# ENGI301_clearasteroids.net
KiCad netlist of a schematic drawn in EAGLE
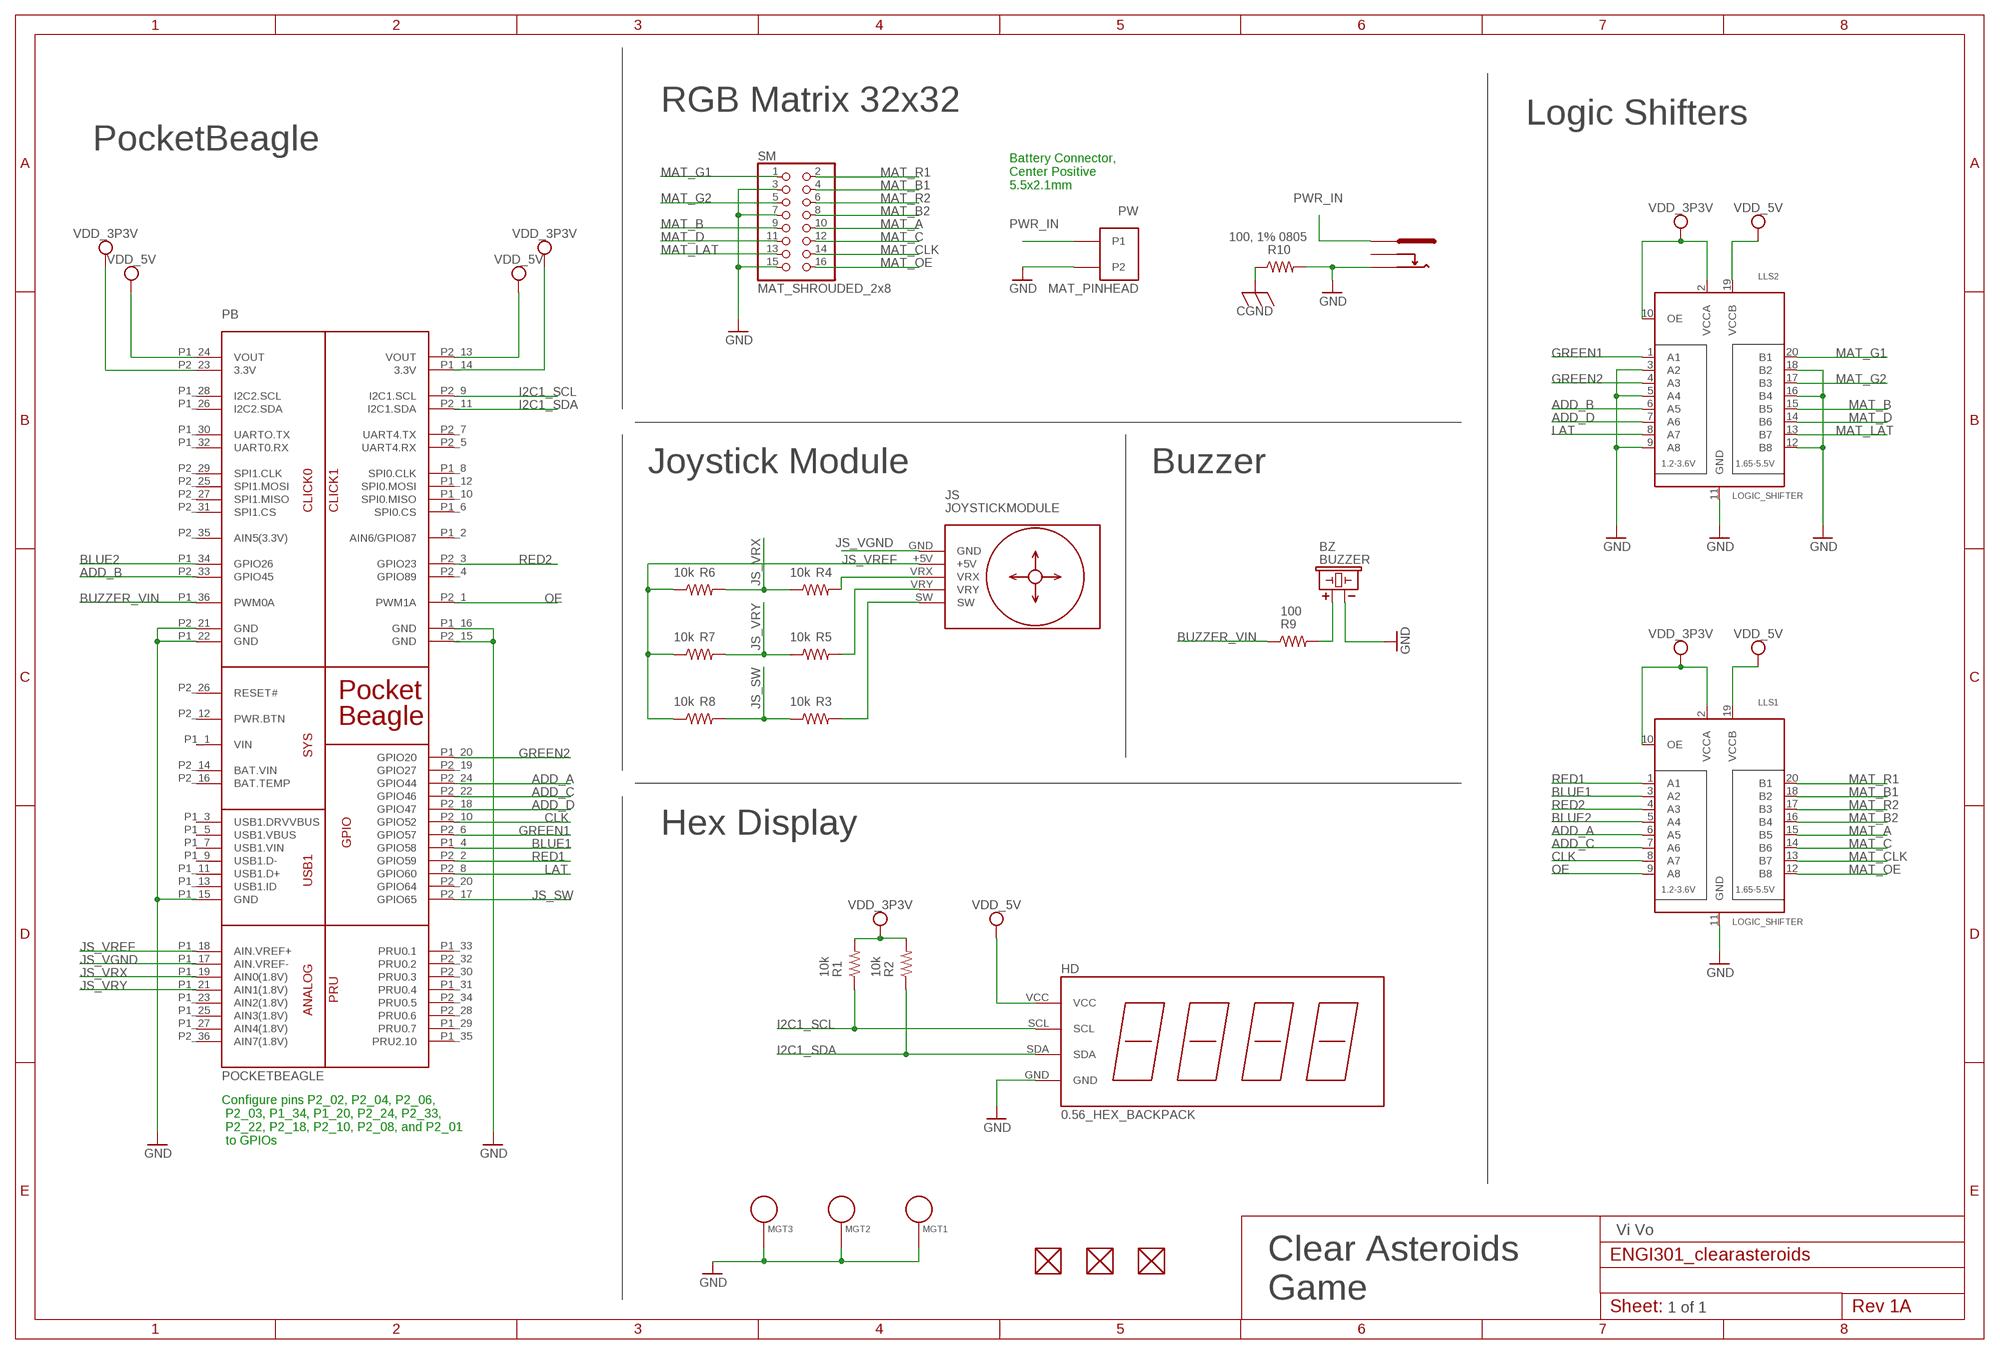
[diagram p0: schematic, sheet 1]

(export (version "E")
  (design (tool "Eeschema 10.0.6"))
  (components
    (comp (ref "BC")
      (value "GHI_PJ-102B_POWER_CON")
      (footprint "eagle-import:GHI_PJ-102B_POWER_CON")
      (libsource (lib "eagle-import") (part "GHI_PJ-102B_POWER_CON"))
    )
    (comp (ref "BZ")
      (value "BUZZER")
      (footprint "eagle-import:BUZZER_6.5MM")
      (libsource (lib "eagle-import") (part "BUZZER"))
    )
    (comp (ref "FUD1")
      (value "FIDUCIAL")
      (footprint "eagle-import:FIDUCIAL_40MIL")
      (libsource (lib "eagle-import") (part "FIDUCIAL"))
    )
    (comp (ref "FUD2")
      (value "FIDUCIAL")
      (footprint "eagle-import:FIDUCIAL_40MIL")
      (libsource (lib "eagle-import") (part "FIDUCIAL"))
    )
    (comp (ref "FUD3")
      (value "FIDUCIAL")
      (footprint "eagle-import:FIDUCIAL_40MIL")
      (libsource (lib "eagle-import") (part "FIDUCIAL"))
    )
    (comp (ref "HD")
      (value "0.56_HEX_BACKPACK")
      (footprint "eagle-import:0.56_HEX_BACKPACK")
      (libsource (lib "eagle-import") (part "0.56_HEX_BACKPACK"))
    )
    (comp (ref "JS")
      (value "JOYSTICKMODULE")
      (footprint "eagle-import:JOYSTICK-MODULE")
      (libsource (lib "eagle-import") (part "JOYSTICKMODULE"))
    )
    (comp (ref "LLS1")
      (value "LOGIC_SHIFTER")
      (footprint "eagle-import:TSSOP20")
      (libsource (lib "eagle-import") (part "TXB0108PWR"))
    )
    (comp (ref "LLS2")
      (value "LOGIC_SHIFTER")
      (footprint "eagle-import:TSSOP20")
      (libsource (lib "eagle-import") (part "TXB0108PWR"))
    )
    (comp (ref "MGT1")
      (value "MOUNTING_HOLE")
      (footprint "eagle-import:MOUNTING_HOLE")
      (libsource (lib "eagle-import") (part "MOUNTING_HOLE"))
    )
    (comp (ref "MGT2")
      (value "MOUNTING_HOLE")
      (footprint "eagle-import:MOUNTING_HOLE")
      (libsource (lib "eagle-import") (part "MOUNTING_HOLE"))
    )
    (comp (ref "MGT3")
      (value "MOUNTING_HOLE")
      (footprint "eagle-import:MOUNTING_HOLE")
      (libsource (lib "eagle-import") (part "MOUNTING_HOLE"))
    )
    (comp (ref "PB")
      (value "POCKETBEAGLE")
      (footprint "eagle-import:POCKETBEAGLE")
      (libsource (lib "eagle-import") (part "POCKETBEAGLE"))
    )
    (comp (ref "PW")
      (value "MAT_PINHEAD")
      (footprint "eagle-import:MSHIELD_TERMBLOCK508")
      (libsource (lib "eagle-import") (part "MAT_PINHEAD"))
    )
    (comp (ref "R1")
      (value "10k")
      (footprint "eagle-import:R1206")
      (libsource (lib "eagle-import") (part "R_R1206"))
    )
    (comp (ref "R2")
      (value "10k")
      (footprint "eagle-import:R1206")
      (libsource (lib "eagle-import") (part "R_R1206"))
    )
    (comp (ref "R3")
      (value "10k")
      (footprint "eagle-import:R1206")
      (libsource (lib "eagle-import") (part "R_R1206"))
    )
    (comp (ref "R4")
      (value "10k")
      (footprint "eagle-import:R1206")
      (libsource (lib "eagle-import") (part "R_R1206"))
    )
    (comp (ref "R5")
      (value "10k")
      (footprint "eagle-import:R1206")
      (libsource (lib "eagle-import") (part "R_R1206"))
    )
    (comp (ref "R6")
      (value "10k")
      (footprint "eagle-import:R1206")
      (libsource (lib "eagle-import") (part "R_R1206"))
    )
    (comp (ref "R7")
      (value "10k")
      (footprint "eagle-import:R1206")
      (libsource (lib "eagle-import") (part "R_R1206"))
    )
    (comp (ref "R8")
      (value "10k")
      (footprint "eagle-import:R1206")
      (libsource (lib "eagle-import") (part "R_R1206"))
    )
    (comp (ref "R9")
      (value "100")
      (footprint "eagle-import:R1206")
      (libsource (lib "eagle-import") (part "R_R1206"))
    )
    (comp (ref "R10")
      (value "100, 1% 0805")
      (footprint "eagle-import:R1206")
      (libsource (lib "eagle-import") (part "R_R1206"))
    )
    (comp (ref "SM")
      (value "MAT_SHROUDED_2x8")
      (footprint "eagle-import:MICROBUILDER_2X08_SHROUDEDSMT")
      (libsource (lib "eagle-import") (part "MICROBUILDER_HEADER-2X8_SHROUDEDSMT"))
    )
  )
  (nets
    (net (code "1") (name "/ADD_A") (class "Default")
      (node (ref "LLS1") (pin "6") (pinfunction "A5_6") (pintype "bidirectional"))
      (node (ref "PB") (pin "P2_24") (pinfunction "GPIO44_P2_24") (pintype "bidirectional"))
    )
    (net (code "2") (name "/ADD_B") (class "Default")
      (node (ref "LLS2") (pin "6") (pinfunction "A5_6") (pintype "bidirectional"))
      (node (ref "PB") (pin "P2_33") (pinfunction "GPIO45_P2_33") (pintype "bidirectional"))
    )
    (net (code "3") (name "/ADD_C") (class "Default")
      (node (ref "LLS1") (pin "7") (pinfunction "A6_7") (pintype "bidirectional"))
      (node (ref "PB") (pin "P2_22") (pinfunction "GPIO46_P2_22") (pintype "bidirectional"))
    )
    (net (code "4") (name "/ADD_D") (class "Default")
      (node (ref "LLS2") (pin "7") (pinfunction "A6_7") (pintype "bidirectional"))
      (node (ref "PB") (pin "P2_18") (pinfunction "GPIO47_P2_18") (pintype "bidirectional"))
    )
    (net (code "5") (name "/BLUE1") (class "Default")
      (node (ref "LLS1") (pin "3") (pinfunction "A2_3") (pintype "bidirectional"))
      (node (ref "PB") (pin "P1_4") (pinfunction "GPIO58_P1_4") (pintype "bidirectional"))
    )
    (net (code "6") (name "/BLUE2") (class "Default")
      (node (ref "LLS1") (pin "5") (pinfunction "A4_5") (pintype "bidirectional"))
      (node (ref "PB") (pin "P1_34") (pinfunction "GPIO26_P1_34") (pintype "bidirectional"))
    )
    (net (code "7") (name "/BUZZER_VIN") (class "Default")
      (node (ref "PB") (pin "P1_36") (pinfunction "PWM0A_P1_36") (pintype "bidirectional"))
      (node (ref "R9") (pin "1") (pinfunction "1_1") (pintype "passive"))
    )
    (net (code "8") (name "/CLK") (class "Default")
      (node (ref "LLS1") (pin "8") (pinfunction "A7_8") (pintype "bidirectional"))
      (node (ref "PB") (pin "P2_10") (pinfunction "GPIO52_P2_10") (pintype "bidirectional"))
    )
    (net (code "9") (name "/GREEN1") (class "Default")
      (node (ref "LLS2") (pin "1") (pinfunction "A1_1") (pintype "bidirectional"))
      (node (ref "PB") (pin "P2_6") (pinfunction "GPIO57_P2_6") (pintype "bidirectional"))
    )
    (net (code "10") (name "/GREEN2") (class "Default")
      (node (ref "LLS2") (pin "4") (pinfunction "A3_4") (pintype "bidirectional"))
      (node (ref "PB") (pin "P1_20") (pinfunction "GPIO20_P1_20") (pintype "bidirectional"))
    )
    (net (code "11") (name "/I2C1_SCL") (class "Default")
      (node (ref "HD") (pin "SCL") (pinfunction "SCL_SCL") (pintype "bidirectional"))
      (node (ref "PB") (pin "P2_9") (pinfunction "I2C1.SCL_P2_9") (pintype "bidirectional"))
      (node (ref "R1") (pin "1") (pinfunction "1_1") (pintype "passive"))
    )
    (net (code "12") (name "/I2C1_SDA") (class "Default")
      (node (ref "HD") (pin "SDA") (pinfunction "SDA_SDA") (pintype "bidirectional"))
      (node (ref "PB") (pin "P2_11") (pinfunction "I2C1.SDA_P2_11") (pintype "bidirectional"))
      (node (ref "R2") (pin "1") (pinfunction "1_1") (pintype "passive"))
    )
    (net (code "13") (name "/JS_SW") (class "Default")
      (node (ref "PB") (pin "P2_17") (pinfunction "GPIO65_P2_17") (pintype "bidirectional"))
      (node (ref "R3") (pin "1") (pinfunction "1_1") (pintype "passive"))
      (node (ref "R8") (pin "2") (pinfunction "2_2") (pintype "passive"))
    )
    (net (code "14") (name "/JS_VGND") (class "Default")
      (node (ref "JS") (pin "GND") (pinfunction "GND_GND") (pintype "power_in"))
      (node (ref "PB") (pin "P1_17") (pinfunction "AIN.VREF-_P1_17") (pintype "bidirectional"))
    )
    (net (code "15") (name "/JS_VREF") (class "Default")
      (node (ref "JS") (pin "+5V") (pinfunction "+5V_+5V") (pintype "power_in"))
      (node (ref "PB") (pin "P1_18") (pinfunction "AIN.VREF+_P1_18") (pintype "bidirectional"))
      (node (ref "R6") (pin "1") (pinfunction "1_1") (pintype "passive"))
      (node (ref "R7") (pin "1") (pinfunction "1_1") (pintype "passive"))
      (node (ref "R8") (pin "1") (pinfunction "1_1") (pintype "passive"))
    )
    (net (code "16") (name "/JS_VRX") (class "Default")
      (node (ref "PB") (pin "P1_19") (pinfunction "AIN0(1.8V)_P1_19") (pintype "bidirectional"))
      (node (ref "R4") (pin "1") (pinfunction "1_1") (pintype "passive"))
      (node (ref "R6") (pin "2") (pinfunction "2_2") (pintype "passive"))
    )
    (net (code "17") (name "/JS_VRY") (class "Default")
      (node (ref "PB") (pin "P1_21") (pinfunction "AIN1(1.8V)_P1_21") (pintype "bidirectional"))
      (node (ref "R5") (pin "1") (pinfunction "1_1") (pintype "passive"))
      (node (ref "R7") (pin "2") (pinfunction "2_2") (pintype "passive"))
    )
    (net (code "18") (name "/LAT") (class "Default")
      (node (ref "LLS2") (pin "8") (pinfunction "A7_8") (pintype "bidirectional"))
      (node (ref "PB") (pin "P2_8") (pinfunction "GPIO60_P2_8") (pintype "bidirectional"))
    )
    (net (code "19") (name "/MAT_A") (class "Default")
      (node (ref "LLS1") (pin "15") (pinfunction "B5_15") (pintype "bidirectional"))
      (node (ref "SM") (pin "10") (pinfunction "10_10") (pintype "passive"))
    )
    (net (code "20") (name "/MAT_B") (class "Default")
      (node (ref "LLS2") (pin "15") (pinfunction "B5_15") (pintype "bidirectional"))
      (node (ref "SM") (pin "9") (pinfunction "9_9") (pintype "passive"))
    )
    (net (code "21") (name "/MAT_B1") (class "Default")
      (node (ref "LLS1") (pin "18") (pinfunction "B2_18") (pintype "bidirectional"))
      (node (ref "SM") (pin "4") (pinfunction "4_4") (pintype "passive"))
    )
    (net (code "22") (name "/MAT_B2") (class "Default")
      (node (ref "LLS1") (pin "16") (pinfunction "B4_16") (pintype "bidirectional"))
      (node (ref "SM") (pin "8") (pinfunction "8_8") (pintype "passive"))
    )
    (net (code "23") (name "/MAT_C") (class "Default")
      (node (ref "LLS1") (pin "14") (pinfunction "B6_14") (pintype "bidirectional"))
      (node (ref "SM") (pin "12") (pinfunction "12_12") (pintype "passive"))
    )
    (net (code "24") (name "/MAT_CLK") (class "Default")
      (node (ref "LLS1") (pin "13") (pinfunction "B7_13") (pintype "bidirectional"))
      (node (ref "SM") (pin "14") (pinfunction "14_14") (pintype "passive"))
    )
    (net (code "25") (name "/MAT_D") (class "Default")
      (node (ref "LLS2") (pin "14") (pinfunction "B6_14") (pintype "bidirectional"))
      (node (ref "SM") (pin "11") (pinfunction "11_11") (pintype "passive"))
    )
    (net (code "26") (name "/MAT_G1") (class "Default")
      (node (ref "LLS2") (pin "20") (pinfunction "B1_20") (pintype "bidirectional"))
      (node (ref "SM") (pin "1") (pinfunction "1_1") (pintype "passive"))
    )
    (net (code "27") (name "/MAT_G2") (class "Default")
      (node (ref "LLS2") (pin "17") (pinfunction "B3_17") (pintype "bidirectional"))
      (node (ref "SM") (pin "5") (pinfunction "5_5") (pintype "passive"))
    )
    (net (code "28") (name "/MAT_LAT") (class "Default")
      (node (ref "LLS2") (pin "13") (pinfunction "B7_13") (pintype "bidirectional"))
      (node (ref "SM") (pin "13") (pinfunction "13_13") (pintype "passive"))
    )
    (net (code "29") (name "/MAT_OE") (class "Default")
      (node (ref "LLS1") (pin "12") (pinfunction "B8_12") (pintype "bidirectional"))
      (node (ref "SM") (pin "16") (pinfunction "16_16") (pintype "passive"))
    )
    (net (code "30") (name "/MAT_R1") (class "Default")
      (node (ref "LLS1") (pin "20") (pinfunction "B1_20") (pintype "bidirectional"))
      (node (ref "SM") (pin "2") (pinfunction "2_2") (pintype "passive"))
    )
    (net (code "31") (name "/MAT_R2") (class "Default")
      (node (ref "LLS1") (pin "17") (pinfunction "B3_17") (pintype "bidirectional"))
      (node (ref "SM") (pin "6") (pinfunction "6_6") (pintype "passive"))
    )
    (net (code "32") (name "/OE") (class "Default")
      (node (ref "LLS1") (pin "9") (pinfunction "A8_9") (pintype "bidirectional"))
      (node (ref "PB") (pin "P2_1") (pinfunction "PWM1A_P2_1") (pintype "bidirectional"))
    )
    (net (code "33") (name "/PWR_IN") (class "Default")
      (node (ref "BC") (pin "IN") (pinfunction "IN_IN") (pintype "bidirectional"))
      (node (ref "PW") (pin "P$3") (pinfunction "P1_P$3") (pintype "bidirectional"))
    )
    (net (code "34") (name "/RED1") (class "Default")
      (node (ref "LLS1") (pin "1") (pinfunction "A1_1") (pintype "bidirectional"))
      (node (ref "PB") (pin "P2_2") (pinfunction "GPIO59_P2_2") (pintype "bidirectional"))
    )
    (net (code "35") (name "/RED2") (class "Default")
      (node (ref "LLS1") (pin "4") (pinfunction "A3_4") (pintype "bidirectional"))
      (node (ref "PB") (pin "P2_3") (pinfunction "GPIO23_P2_3") (pintype "bidirectional"))
    )
    (net (code "36") (name "CGND") (class "Default")
      (node (ref "R10") (pin "1") (pinfunction "1_1") (pintype "passive"))
    )
    (net (code "37") (name "GND") (class "Default")
      (node (ref "BC") (pin "OUT") (pinfunction "OUT_OUT") (pintype "bidirectional"))
      (node (ref "BZ") (pin "-") (pinfunction "-_-") (pintype "passive"))
      (node (ref "HD") (pin "GND") (pinfunction "GND_GND") (pintype "bidirectional"))
      (node (ref "LLS1") (pin "11") (pinfunction "GND_11") (pintype "bidirectional"))
      (node (ref "LLS2") (pin "11") (pinfunction "GND_11") (pintype "bidirectional"))
      (node (ref "LLS2") (pin "12") (pinfunction "B8_12") (pintype "bidirectional"))
      (node (ref "LLS2") (pin "16") (pinfunction "B4_16") (pintype "bidirectional"))
      (node (ref "LLS2") (pin "18") (pinfunction "B2_18") (pintype "bidirectional"))
      (node (ref "LLS2") (pin "3") (pinfunction "A2_3") (pintype "bidirectional"))
      (node (ref "LLS2") (pin "5") (pinfunction "A4_5") (pintype "bidirectional"))
      (node (ref "LLS2") (pin "9") (pinfunction "A8_9") (pintype "bidirectional"))
      (node (ref "MGT1") (pin "P$1") (pinfunction "P$1_P$1") (pintype "bidirectional"))
      (node (ref "MGT2") (pin "P$1") (pinfunction "P$1_P$1") (pintype "bidirectional"))
      (node (ref "MGT3") (pin "P$1") (pinfunction "P$1_P$1") (pintype "bidirectional"))
      (node (ref "PB") (pin "P1_15") (pinfunction "GND_P1_15") (pintype "bidirectional"))
      (node (ref "PB") (pin "P1_16") (pinfunction "GND_P1_16") (pintype "bidirectional"))
      (node (ref "PB") (pin "P1_22") (pinfunction "GND_P1_22") (pintype "bidirectional"))
      (node (ref "PB") (pin "P2_15") (pinfunction "GND_P2_15") (pintype "bidirectional"))
      (node (ref "PB") (pin "P2_21") (pinfunction "GND_P2_21") (pintype "bidirectional"))
      (node (ref "PW") (pin "P$4") (pinfunction "P2_P$4") (pintype "bidirectional"))
      (node (ref "R10") (pin "2") (pinfunction "2_2") (pintype "passive"))
      (node (ref "SM") (pin "15") (pinfunction "15_15") (pintype "passive"))
      (node (ref "SM") (pin "3") (pinfunction "3_3") (pintype "passive"))
      (node (ref "SM") (pin "7") (pinfunction "7_7") (pintype "passive"))
    )
    (net (code "38") (name "Net-(BZ-Pad+)") (class "Default")
      (node (ref "BZ") (pin "+") (pinfunction "+_+") (pintype "passive"))
      (node (ref "R9") (pin "2") (pinfunction "2_2") (pintype "passive"))
    )
    (net (code "39") (name "Net-(JS-PadSW)") (class "Default")
      (node (ref "JS") (pin "SW") (pinfunction "SW_SW") (pintype "passive"))
      (node (ref "R3") (pin "2") (pinfunction "2_2") (pintype "passive"))
    )
    (net (code "40") (name "Net-(JS-PadVRX)") (class "Default")
      (node (ref "JS") (pin "VRX") (pinfunction "VRX_VRX") (pintype "passive"))
      (node (ref "R4") (pin "2") (pinfunction "2_2") (pintype "passive"))
    )
    (net (code "41") (name "Net-(JS-PadVRY)") (class "Default")
      (node (ref "JS") (pin "VRY") (pinfunction "VRY_VRY") (pintype "passive"))
      (node (ref "R5") (pin "2") (pinfunction "2_2") (pintype "passive"))
    )
    (net (code "42") (name "VDD_3P3V") (class "Default")
      (node (ref "LLS1") (pin "10") (pinfunction "OE_10") (pintype "bidirectional"))
      (node (ref "LLS1") (pin "2") (pinfunction "VCCA_2") (pintype "bidirectional"))
      (node (ref "LLS2") (pin "10") (pinfunction "OE_10") (pintype "bidirectional"))
      (node (ref "LLS2") (pin "2") (pinfunction "VCCA_2") (pintype "bidirectional"))
      (node (ref "PB") (pin "P1_14") (pinfunction "3.3V_P1_14") (pintype "bidirectional"))
      (node (ref "PB") (pin "P2_23") (pinfunction "3.3V_P2_23") (pintype "bidirectional"))
      (node (ref "R1") (pin "2") (pinfunction "2_2") (pintype "passive"))
      (node (ref "R2") (pin "2") (pinfunction "2_2") (pintype "passive"))
    )
    (net (code "43") (name "VDD_5V") (class "Default")
      (node (ref "HD") (pin "VCC") (pinfunction "VCC_VCC") (pintype "power_in"))
      (node (ref "LLS1") (pin "19") (pinfunction "VCCB_19") (pintype "bidirectional"))
      (node (ref "LLS2") (pin "19") (pinfunction "VCCB_19") (pintype "bidirectional"))
      (node (ref "PB") (pin "P1_24") (pinfunction "VOUT_P1_24") (pintype "bidirectional"))
      (node (ref "PB") (pin "P2_13") (pinfunction "VOUT_P2_13") (pintype "bidirectional"))
    )
    (net (code "44") (name "unconnected-(BC-PadOUT_CON)") (class "Default")
      (node (ref "BC") (pin "OUT_CON") (pinfunction "OUT_CON_OUT_CON") (pintype "bidirectional"))
    )
    (net (code "45") (name "unconnected-(FUD1-PadP$1)") (class "Default")
      (node (ref "FUD1") (pin "P$1") (pinfunction "P$1_P$1") (pintype "no_connect"))
    )
    (net (code "46") (name "unconnected-(FUD2-PadP$1)") (class "Default")
      (node (ref "FUD2") (pin "P$1") (pinfunction "P$1_P$1") (pintype "no_connect"))
    )
    (net (code "47") (name "unconnected-(FUD3-PadP$1)") (class "Default")
      (node (ref "FUD3") (pin "P$1") (pinfunction "P$1_P$1") (pintype "no_connect"))
    )
    (net (code "48") (name "unconnected-(PB-AIN2(1.8V)-PadP1_23)") (class "Default")
      (node (ref "PB") (pin "P1_23") (pinfunction "AIN2(1.8V)_P1_23") (pintype "bidirectional"))
    )
    (net (code "49") (name "unconnected-(PB-AIN3(1.8V)-PadP1_25)") (class "Default")
      (node (ref "PB") (pin "P1_25") (pinfunction "AIN3(1.8V)_P1_25") (pintype "bidirectional"))
    )
    (net (code "50") (name "unconnected-(PB-AIN4(1.8V)-PadP1_27)") (class "Default")
      (node (ref "PB") (pin "P1_27") (pinfunction "AIN4(1.8V)_P1_27") (pintype "bidirectional"))
    )
    (net (code "51") (name "unconnected-(PB-AIN5(3.3V)-PadP2_35)") (class "Default")
      (node (ref "PB") (pin "P2_35") (pinfunction "AIN5(3.3V)_P2_35") (pintype "bidirectional"))
    )
    (net (code "52") (name "unconnected-(PB-AIN6{slash}GPIO87-PadP1_2)") (class "Default")
      (node (ref "PB") (pin "P1_2") (pinfunction "AIN6/GPIO87_P1_2") (pintype "bidirectional"))
    )
    (net (code "53") (name "unconnected-(PB-AIN7(1.8V)-PadP2_36)") (class "Default")
      (node (ref "PB") (pin "P2_36") (pinfunction "AIN7(1.8V)_P2_36") (pintype "bidirectional"))
    )
    (net (code "54") (name "unconnected-(PB-BAT.TEMP-PadP2_16)") (class "Default")
      (node (ref "PB") (pin "P2_16") (pinfunction "BAT.TEMP_P2_16") (pintype "bidirectional"))
    )
    (net (code "55") (name "unconnected-(PB-BAT.VIN-PadP2_14)") (class "Default")
      (node (ref "PB") (pin "P2_14") (pinfunction "BAT.VIN_P2_14") (pintype "bidirectional"))
    )
    (net (code "56") (name "unconnected-(PB-GPIO27-PadP2_19)") (class "Default")
      (node (ref "PB") (pin "P2_19") (pinfunction "GPIO27_P2_19") (pintype "bidirectional"))
    )
    (net (code "57") (name "unconnected-(PB-GPIO64-PadP2_20)") (class "Default")
      (node (ref "PB") (pin "P2_20") (pinfunction "GPIO64_P2_20") (pintype "bidirectional"))
    )
    (net (code "58") (name "unconnected-(PB-GPIO89-PadP2_4)") (class "Default")
      (node (ref "PB") (pin "P2_4") (pinfunction "GPIO89_P2_4") (pintype "bidirectional"))
    )
    (net (code "59") (name "unconnected-(PB-I2C2.SCL-PadP1_28)") (class "Default")
      (node (ref "PB") (pin "P1_28") (pinfunction "I2C2.SCL_P1_28") (pintype "bidirectional"))
    )
    (net (code "60") (name "unconnected-(PB-I2C2.SDA-PadP1_26)") (class "Default")
      (node (ref "PB") (pin "P1_26") (pinfunction "I2C2.SDA_P1_26") (pintype "bidirectional"))
    )
    (net (code "61") (name "unconnected-(PB-PRU0.1-PadP1_33)") (class "Default")
      (node (ref "PB") (pin "P1_33") (pinfunction "PRU0.1_P1_33") (pintype "bidirectional"))
    )
    (net (code "62") (name "unconnected-(PB-PRU0.2-PadP2_32)") (class "Default")
      (node (ref "PB") (pin "P2_32") (pinfunction "PRU0.2_P2_32") (pintype "bidirectional"))
    )
    (net (code "63") (name "unconnected-(PB-PRU0.3-PadP2_30)") (class "Default")
      (node (ref "PB") (pin "P2_30") (pinfunction "PRU0.3_P2_30") (pintype "bidirectional"))
    )
    (net (code "64") (name "unconnected-(PB-PRU0.4-PadP1_31)") (class "Default")
      (node (ref "PB") (pin "P1_31") (pinfunction "PRU0.4_P1_31") (pintype "bidirectional"))
    )
    (net (code "65") (name "unconnected-(PB-PRU0.5-PadP2_34)") (class "Default")
      (node (ref "PB") (pin "P2_34") (pinfunction "PRU0.5_P2_34") (pintype "bidirectional"))
    )
    (net (code "66") (name "unconnected-(PB-PRU0.6-PadP2_28)") (class "Default")
      (node (ref "PB") (pin "P2_28") (pinfunction "PRU0.6_P2_28") (pintype "bidirectional"))
    )
    (net (code "67") (name "unconnected-(PB-PRU0.7-PadP1_29)") (class "Default")
      (node (ref "PB") (pin "P1_29") (pinfunction "PRU0.7_P1_29") (pintype "bidirectional"))
    )
    (net (code "68") (name "unconnected-(PB-PRU2.10-PadP1_35)") (class "Default")
      (node (ref "PB") (pin "P1_35") (pinfunction "PRU2.10_P1_35") (pintype "bidirectional"))
    )
    (net (code "69") (name "unconnected-(PB-PWR.BTN-PadP2_12)") (class "Default")
      (node (ref "PB") (pin "P2_12") (pinfunction "PWR.BTN_P2_12") (pintype "bidirectional"))
    )
    (net (code "70") (name "unconnected-(PB-RESET#-PadP2_26)") (class "Default")
      (node (ref "PB") (pin "P2_26") (pinfunction "RESET#_P2_26") (pintype "bidirectional"))
    )
    (net (code "71") (name "unconnected-(PB-SPI0.CLK-PadP1_8)") (class "Default")
      (node (ref "PB") (pin "P1_8") (pinfunction "SPI0.CLK_P1_8") (pintype "bidirectional"))
    )
    (net (code "72") (name "unconnected-(PB-SPI0.CS-PadP1_6)") (class "Default")
      (node (ref "PB") (pin "P1_6") (pinfunction "SPI0.CS_P1_6") (pintype "bidirectional"))
    )
    (net (code "73") (name "unconnected-(PB-SPI0.MISO-PadP1_10)") (class "Default")
      (node (ref "PB") (pin "P1_10") (pinfunction "SPI0.MISO_P1_10") (pintype "bidirectional"))
    )
    (net (code "74") (name "unconnected-(PB-SPI0.MOSI-PadP1_12)") (class "Default")
      (node (ref "PB") (pin "P1_12") (pinfunction "SPI0.MOSI_P1_12") (pintype "bidirectional"))
    )
    (net (code "75") (name "unconnected-(PB-SPI1.CLK-PadP2_29)") (class "Default")
      (node (ref "PB") (pin "P2_29") (pinfunction "SPI1.CLK_P2_29") (pintype "bidirectional"))
    )
    (net (code "76") (name "unconnected-(PB-SPI1.CS-PadP2_31)") (class "Default")
      (node (ref "PB") (pin "P2_31") (pinfunction "SPI1.CS_P2_31") (pintype "bidirectional"))
    )
    (net (code "77") (name "unconnected-(PB-SPI1.MISO-PadP2_27)") (class "Default")
      (node (ref "PB") (pin "P2_27") (pinfunction "SPI1.MISO_P2_27") (pintype "bidirectional"))
    )
    (net (code "78") (name "unconnected-(PB-SPI1.MOSI-PadP2_25)") (class "Default")
      (node (ref "PB") (pin "P2_25") (pinfunction "SPI1.MOSI_P2_25") (pintype "bidirectional"))
    )
    (net (code "79") (name "unconnected-(PB-UART0.RX-PadP1_32)") (class "Default")
      (node (ref "PB") (pin "P1_32") (pinfunction "UART0.RX_P1_32") (pintype "bidirectional"))
    )
    (net (code "80") (name "unconnected-(PB-UART4.RX-PadP2_5)") (class "Default")
      (node (ref "PB") (pin "P2_5") (pinfunction "UART4.RX_P2_5") (pintype "bidirectional"))
    )
    (net (code "81") (name "unconnected-(PB-UART4.TX-PadP2_7)") (class "Default")
      (node (ref "PB") (pin "P2_7") (pinfunction "UART4.TX_P2_7") (pintype "bidirectional"))
    )
    (net (code "82") (name "unconnected-(PB-UARTO.TX-PadP1_30)") (class "Default")
      (node (ref "PB") (pin "P1_30") (pinfunction "UARTO.TX_P1_30") (pintype "bidirectional"))
    )
    (net (code "83") (name "unconnected-(PB-USB1.D+-PadP1_11)") (class "Default")
      (node (ref "PB") (pin "P1_11") (pinfunction "USB1.D+_P1_11") (pintype "bidirectional"))
    )
    (net (code "84") (name "unconnected-(PB-USB1.D--PadP1_9)") (class "Default")
      (node (ref "PB") (pin "P1_9") (pinfunction "USB1.D-_P1_9") (pintype "bidirectional"))
    )
    (net (code "85") (name "unconnected-(PB-USB1.DRVVBUS-PadP1_3)") (class "Default")
      (node (ref "PB") (pin "P1_3") (pinfunction "USB1.DRVVBUS_P1_3") (pintype "bidirectional"))
    )
    (net (code "86") (name "unconnected-(PB-USB1.ID-PadP1_13)") (class "Default")
      (node (ref "PB") (pin "P1_13") (pinfunction "USB1.ID_P1_13") (pintype "bidirectional"))
    )
    (net (code "87") (name "unconnected-(PB-USB1.VBUS-PadP1_5)") (class "Default")
      (node (ref "PB") (pin "P1_5") (pinfunction "USB1.VBUS_P1_5") (pintype "bidirectional"))
    )
    (net (code "88") (name "unconnected-(PB-USB1.VIN-PadP1_7)") (class "Default")
      (node (ref "PB") (pin "P1_7") (pinfunction "USB1.VIN_P1_7") (pintype "bidirectional"))
    )
    (net (code "89") (name "unconnected-(PB-VIN-PadP1_1)") (class "Default")
      (node (ref "PB") (pin "P1_1") (pinfunction "VIN_P1_1") (pintype "bidirectional"))
    )
  )
)
